# sensor_schematic.net
KiCad netlist of a schematic drawn in EAGLE
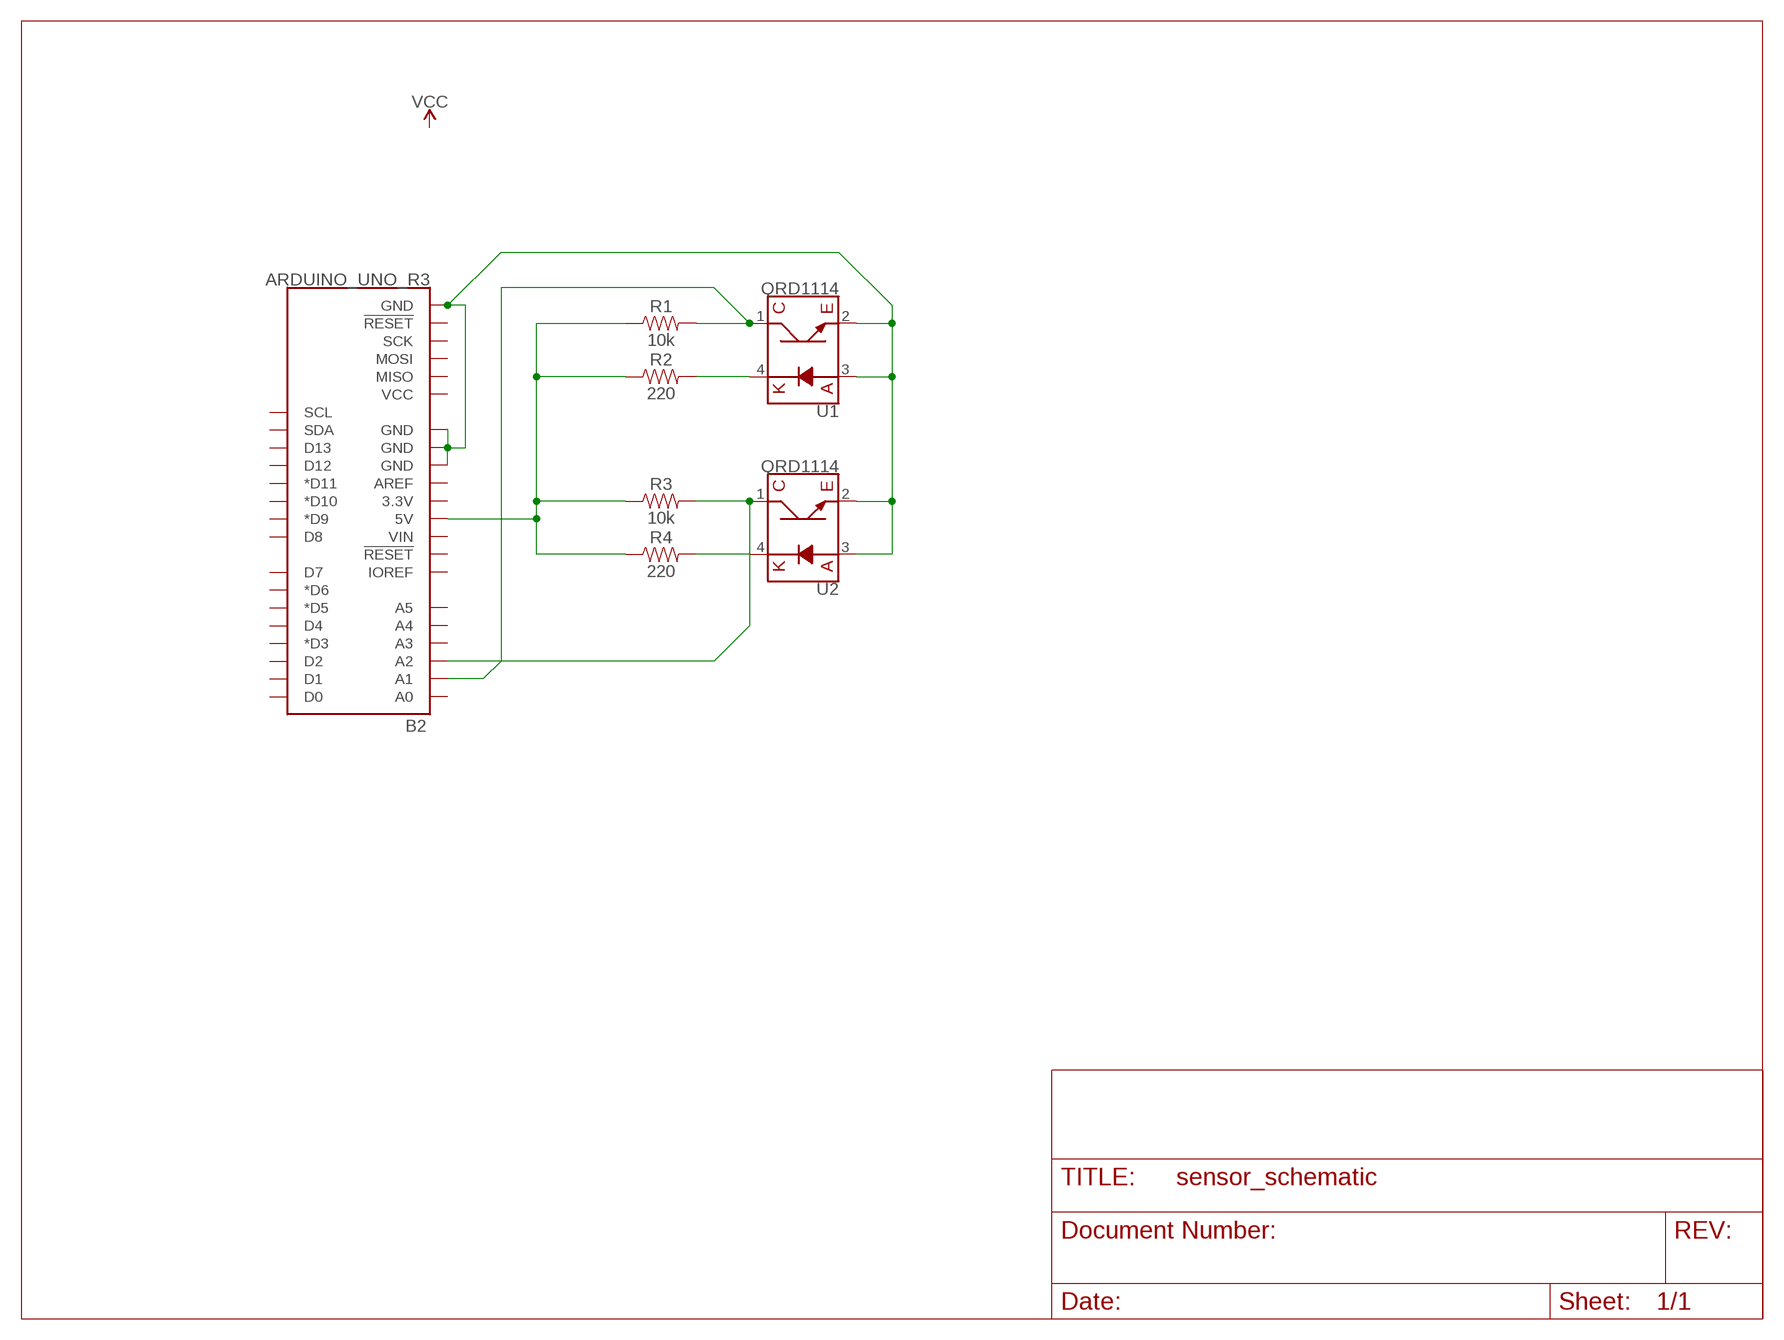
[diagram p0: schematic, sheet 1]

(export (version "E")
  (design (tool "Eeschema 10.0.6"))
  (components
    (comp (ref "B2")
      (value "ARDUINO_UNO_R3")
      (footprint "eagle-import:ARDUINO_R3")
      (libsource (lib "eagle-import") (part "ARDUINO_UNO_R3"))
    )
    (comp (ref "R1")
      (value "10k")
      (footprint "eagle-import:AXIAL-0.3")
      (libsource (lib "eagle-import") (part "1KOHM-HORIZ-1/4W-1%"))
    )
    (comp (ref "R2")
      (value "220")
      (footprint "eagle-import:AXIAL-0.3")
      (libsource (lib "eagle-import") (part "1KOHM-HORIZ-1/4W-1%"))
    )
    (comp (ref "R3")
      (value "10k")
      (footprint "eagle-import:AXIAL-0.3")
      (libsource (lib "eagle-import") (part "1KOHM-HORIZ-1/4W-1%"))
    )
    (comp (ref "R4")
      (value "220")
      (footprint "eagle-import:AXIAL-0.3")
      (libsource (lib "eagle-import") (part "1KOHM-HORIZ-1/4W-1%"))
    )
    (comp (ref "U1")
      (value "QRD1114")
      (footprint "eagle-import:QRD1114")
      (libsource (lib "eagle-import") (part "QRD1114"))
    )
    (comp (ref "U2")
      (value "QRD1114")
      (footprint "eagle-import:QRD1114")
      (libsource (lib "eagle-import") (part "QRD1114"))
    )
  )
  (nets
    (net (code "1") (name "Net-(R1-1)") (class "Default")
      (node (ref "B2") (pin "5V") (pinfunction "5V_5V") (pintype "bidirectional"))
      (node (ref "R1") (pin "P$1") (pinfunction "1_P$1") (pintype "passive"))
      (node (ref "R2") (pin "P$1") (pinfunction "1_P$1") (pintype "passive"))
      (node (ref "R3") (pin "P$1") (pinfunction "1_P$1") (pintype "passive"))
      (node (ref "R4") (pin "P$1") (pinfunction "1_P$1") (pintype "passive"))
    )
    (net (code "2") (name "Net-(R1-2)") (class "Default")
      (node (ref "B2") (pin "A1") (pinfunction "A1_A1") (pintype "bidirectional"))
      (node (ref "R1") (pin "P$2") (pinfunction "2_P$2") (pintype "passive"))
      (node (ref "U1") (pin "1") (pinfunction "C_1") (pintype "bidirectional"))
    )
    (net (code "3") (name "Net-(R2-2)") (class "Default")
      (node (ref "R2") (pin "P$2") (pinfunction "2_P$2") (pintype "passive"))
      (node (ref "U1") (pin "4") (pinfunction "K_4") (pintype "bidirectional"))
    )
    (net (code "4") (name "Net-(R3-2)") (class "Default")
      (node (ref "B2") (pin "A2") (pinfunction "A2_A2") (pintype "bidirectional"))
      (node (ref "R3") (pin "P$2") (pinfunction "2_P$2") (pintype "passive"))
      (node (ref "U2") (pin "1") (pinfunction "C_1") (pintype "bidirectional"))
    )
    (net (code "5") (name "Net-(R4-2)") (class "Default")
      (node (ref "R4") (pin "P$2") (pinfunction "2_P$2") (pintype "passive"))
      (node (ref "U2") (pin "4") (pinfunction "K_4") (pintype "bidirectional"))
    )
    (net (code "6") (name "Net-(U1-A)") (class "Default")
      (node (ref "B2") (pin "GND@1") (pinfunction "GND_GND@1") (pintype "bidirectional"))
      (node (ref "B2") (pin "GND@2") (pinfunction "GND_GND@2") (pintype "bidirectional"))
      (node (ref "B2") (pin "GND@3") (pinfunction "GND_GND@3") (pintype "bidirectional"))
      (node (ref "B2") (pin "GND@4") (pinfunction "GND_GND@4") (pintype "bidirectional"))
      (node (ref "U1") (pin "2") (pinfunction "E_2") (pintype "bidirectional"))
      (node (ref "U1") (pin "3") (pinfunction "A_3") (pintype "bidirectional"))
      (node (ref "U2") (pin "2") (pinfunction "E_2") (pintype "bidirectional"))
      (node (ref "U2") (pin "3") (pinfunction "A_3") (pintype "bidirectional"))
    )
    (net (code "8") (name "unconnected-(B2-*D3-PadD3)") (class "Default")
      (node (ref "B2") (pin "D3") (pinfunction "*D3_D3") (pintype "bidirectional"))
    )
    (net (code "9") (name "unconnected-(B2-*D5-PadD5)") (class "Default")
      (node (ref "B2") (pin "D5") (pinfunction "*D5_D5") (pintype "bidirectional"))
    )
    (net (code "10") (name "unconnected-(B2-*D6-PadD6)") (class "Default")
      (node (ref "B2") (pin "D6") (pinfunction "*D6_D6") (pintype "bidirectional"))
    )
    (net (code "11") (name "unconnected-(B2-*D9-PadD9)") (class "Default")
      (node (ref "B2") (pin "D9") (pinfunction "*D9_D9") (pintype "bidirectional"))
    )
    (net (code "12") (name "unconnected-(B2-*D10-PadD10)") (class "Default")
      (node (ref "B2") (pin "D10") (pinfunction "*D10_D10") (pintype "bidirectional"))
    )
    (net (code "13") (name "unconnected-(B2-*D11-PadD11)") (class "Default")
      (node (ref "B2") (pin "D11") (pinfunction "*D11_D11") (pintype "bidirectional"))
    )
    (net (code "14") (name "unconnected-(B2-Pad3.3V)") (class "Default")
      (node (ref "B2") (pin "3.3V") (pinfunction "3.3V_3.3V") (pintype "bidirectional"))
    )
    (net (code "15") (name "unconnected-(B2-PadA0)") (class "Default")
      (node (ref "B2") (pin "A0") (pinfunction "A0_A0") (pintype "bidirectional"))
    )
    (net (code "16") (name "unconnected-(B2-PadA3)") (class "Default")
      (node (ref "B2") (pin "A3") (pinfunction "A3_A3") (pintype "bidirectional"))
    )
    (net (code "17") (name "unconnected-(B2-PadA4)") (class "Default")
      (node (ref "B2") (pin "A4") (pinfunction "A4_A4") (pintype "bidirectional"))
    )
    (net (code "18") (name "unconnected-(B2-PadA5)") (class "Default")
      (node (ref "B2") (pin "A5") (pinfunction "A5_A5") (pintype "bidirectional"))
    )
    (net (code "19") (name "unconnected-(B2-PadAREF)") (class "Default")
      (node (ref "B2") (pin "AREF") (pinfunction "AREF_AREF") (pintype "bidirectional"))
    )
    (net (code "20") (name "unconnected-(B2-PadD0)") (class "Default")
      (node (ref "B2") (pin "D0") (pinfunction "D0_D0") (pintype "bidirectional"))
    )
    (net (code "21") (name "unconnected-(B2-PadD1)") (class "Default")
      (node (ref "B2") (pin "D1") (pinfunction "D1_D1") (pintype "bidirectional"))
    )
    (net (code "22") (name "unconnected-(B2-PadD2)") (class "Default")
      (node (ref "B2") (pin "D2") (pinfunction "D2_D2") (pintype "bidirectional"))
    )
    (net (code "23") (name "unconnected-(B2-PadD4)") (class "Default")
      (node (ref "B2") (pin "D4") (pinfunction "D4_D4") (pintype "bidirectional"))
    )
    (net (code "24") (name "unconnected-(B2-PadD7)") (class "Default")
      (node (ref "B2") (pin "D7") (pinfunction "D7_D7") (pintype "bidirectional"))
    )
    (net (code "25") (name "unconnected-(B2-PadD8)") (class "Default")
      (node (ref "B2") (pin "D8") (pinfunction "D8_D8") (pintype "bidirectional"))
    )
    (net (code "26") (name "unconnected-(B2-PadD12)") (class "Default")
      (node (ref "B2") (pin "D12") (pinfunction "D12_D12") (pintype "bidirectional"))
    )
    (net (code "27") (name "unconnected-(B2-PadD13)") (class "Default")
      (node (ref "B2") (pin "D13") (pinfunction "D13_D13") (pintype "bidirectional"))
    )
    (net (code "28") (name "unconnected-(B2-PadIOREF)") (class "Default")
      (node (ref "B2") (pin "IOREF") (pinfunction "IOREF_IOREF") (pintype "bidirectional"))
    )
    (net (code "29") (name "unconnected-(B2-PadMISO)") (class "Default")
      (node (ref "B2") (pin "MISO") (pinfunction "MISO_MISO") (pintype "bidirectional"))
    )
    (net (code "30") (name "unconnected-(B2-PadMOSI)") (class "Default")
      (node (ref "B2") (pin "MOSI") (pinfunction "MOSI_MOSI") (pintype "bidirectional"))
    )
    (net (code "31") (name "unconnected-(B2-PadSCK)") (class "Default")
      (node (ref "B2") (pin "SCK") (pinfunction "SCK_SCK") (pintype "bidirectional"))
    )
    (net (code "32") (name "unconnected-(B2-PadSCL)") (class "Default")
      (node (ref "B2") (pin "SCL") (pinfunction "SCL_SCL") (pintype "bidirectional"))
    )
    (net (code "33") (name "unconnected-(B2-PadSDA)") (class "Default")
      (node (ref "B2") (pin "SDA") (pinfunction "SDA_SDA") (pintype "bidirectional"))
    )
    (net (code "34") (name "unconnected-(B2-PadVCC)") (class "Default")
      (node (ref "B2") (pin "VCC") (pinfunction "VCC_VCC") (pintype "bidirectional"))
    )
    (net (code "35") (name "unconnected-(B2-PadVIN)") (class "Default")
      (node (ref "B2") (pin "VIN") (pinfunction "VIN_VIN") (pintype "bidirectional"))
    )
    (net (code "36") (name "unconnected-(B2-~{RESET}-PadRESET@1)") (class "Default")
      (node (ref "B2") (pin "RESET@1") (pinfunction "~{RESET}_RESET@1") (pintype "bidirectional"))
    )
    (net (code "37") (name "unconnected-(B2-~{RESET}-PadRESET@2)") (class "Default")
      (node (ref "B2") (pin "RESET@2") (pinfunction "~{RESET}_RESET@2") (pintype "bidirectional"))
    )
  )
)
